# TOP.net
KiCad netlist of a schematic drawn in Altium Designer
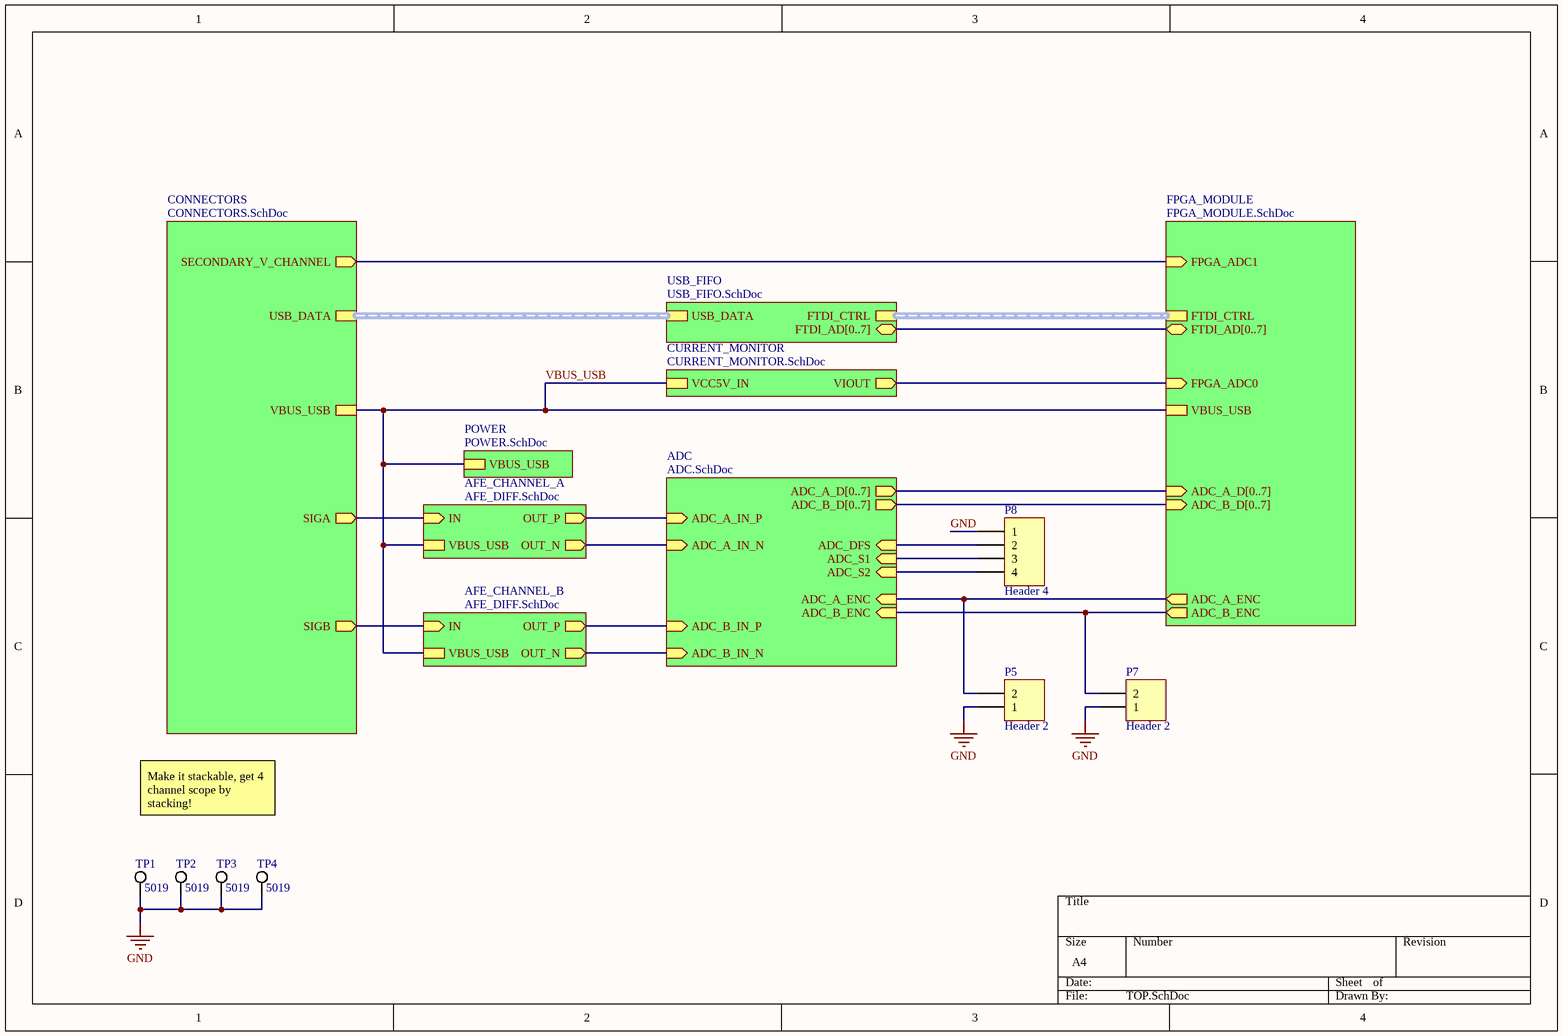
[diagram p0: TOP.SchDoc]

(export (version "E")
  (design (tool "Eeschema 10.0.6"))
  (components
    (comp (ref "P5")
      (value "Header 2")
      (footprint "HDR1X2")
      (description "Header, 2-Pin")
      (fields (field (name "PUBLISHER") "Altium Limited"))
      (libsource (lib "Miscellaneous Connectors") (part "Header 2"))
    )
    (comp (ref "P7")
      (value "Header 2")
      (footprint "HDR1X2")
      (description "Header, 2-Pin")
      (fields (field (name "PUBLISHER") "Altium Limited"))
      (libsource (lib "Miscellaneous Connectors") (part "Header 2"))
    )
    (comp (ref "P8")
      (value "Header 4")
      (footprint "HDR1X4")
      (description "Header, 4-Pin")
      (fields (field (name "PUBLISHER") "Altium Limited"))
      (libsource (lib "Miscellaneous Connectors") (part "Header 4"))
    )
    (comp (ref "TP1")
      (value "5019")
      (footprint "KSTN-5019_V")
      (description "Test Point, 1 Position SMD, RoHS, Tape and Reel")
      (libsource (lib "Altium Content Vault") (part "TESTPOINT_WHITE"))
    )
    (comp (ref "TP2")
      (value "5019")
      (footprint "KSTN-5019_V")
      (description "Test Point, 1 Position SMD, RoHS, Tape and Reel")
      (libsource (lib "Altium Content Vault") (part "TESTPOINT_WHITE"))
    )
    (comp (ref "TP3")
      (value "5019")
      (footprint "KSTN-5019_V")
      (description "Test Point, 1 Position SMD, RoHS, Tape and Reel")
      (libsource (lib "Altium Content Vault") (part "TESTPOINT_WHITE"))
    )
    (comp (ref "TP4")
      (value "5019")
      (footprint "KSTN-5019_V")
      (description "Test Point, 1 Position SMD, RoHS, Tape and Reel")
      (libsource (lib "Altium Content Vault") (part "TESTPOINT_WHITE"))
    )
  )
  (nets
    (net (code "2") (name "/ADC_A_ENC") (class "Default")
      (node (ref "P5") (pin "2") (pinfunction "2_2") (pintype "passive"))
    )
    (net (code "4") (name "/ADC_B_ENC") (class "Default")
      (node (ref "P7") (pin "2") (pinfunction "2_2") (pintype "passive"))
    )
    (net (code "5") (name "/ADC_DFS") (class "Default")
      (node (ref "P8") (pin "2") (pinfunction "2_2") (pintype "passive"))
    )
    (net (code "6") (name "/ADC_S1") (class "Default")
      (node (ref "P8") (pin "3") (pinfunction "3_3") (pintype "passive"))
    )
    (net (code "7") (name "/ADC_S2") (class "Default")
      (node (ref "P8") (pin "4") (pinfunction "4_4") (pintype "passive"))
    )
    (net (code "20") (name "GND") (class "Default")
      (node (ref "P5") (pin "1") (pinfunction "1_1") (pintype "passive"))
      (node (ref "P7") (pin "1") (pinfunction "1_1") (pintype "passive"))
      (node (ref "P8") (pin "1") (pinfunction "1_1") (pintype "passive"))
      (node (ref "TP1") (pin "1") (pinfunction "1_1") (pintype "passive"))
      (node (ref "TP2") (pin "1") (pinfunction "1_1") (pintype "passive"))
      (node (ref "TP3") (pin "1") (pinfunction "1_1") (pintype "passive"))
      (node (ref "TP4") (pin "1") (pinfunction "1_1") (pintype "passive"))
    )
  )
)
